# acrylic-sign_schematic.net
KiCad netlist of a schematic drawn in EAGLE
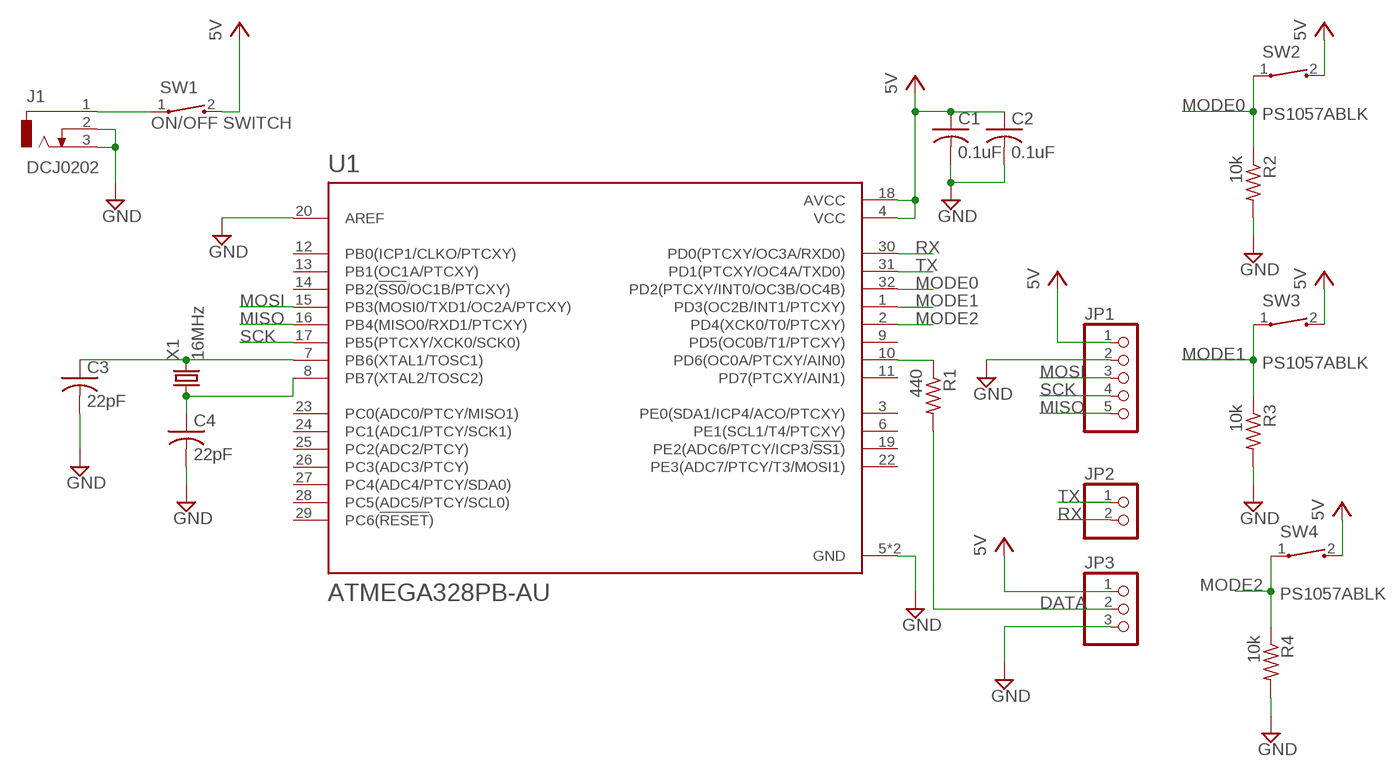
[diagram p0: schematic, sheet 1]

(export (version "E")
  (design (tool "Eeschema 10.0.6"))
  (components
    (comp (ref "C1")
      (value "0.1uF")
      (footprint "eagle-import:C0603")
      (libsource (lib "eagle-import") (part "C-USC0603"))
    )
    (comp (ref "C2")
      (value "0.1uF")
      (footprint "eagle-import:C0603")
      (libsource (lib "eagle-import") (part "C-USC0603"))
    )
    (comp (ref "C3")
      (value "22pF")
      (footprint "eagle-import:C0603")
      (libsource (lib "eagle-import") (part "C-USC0603"))
    )
    (comp (ref "C4")
      (value "22pF")
      (footprint "eagle-import:C0603")
      (libsource (lib "eagle-import") (part "C-USC0603"))
    )
    (comp (ref "J1")
      (value "DCJ0202")
      (footprint "eagle-import:DCJ0202")
      (libsource (lib "eagle-import") (part "DCJ0202"))
    )
    (comp (ref "JP1")
      (value "PINHD-1X5")
      (footprint "eagle-import:1X05")
      (libsource (lib "eagle-import") (part "PINHD-1X5"))
    )
    (comp (ref "JP2")
      (value "PINHD-1X2")
      (footprint "eagle-import:1X02")
      (libsource (lib "eagle-import") (part "PINHD-1X2"))
    )
    (comp (ref "JP3")
      (value "PINHD-1X3")
      (footprint "eagle-import:1X03")
      (libsource (lib "eagle-import") (part "PINHD-1X3"))
    )
    (comp (ref "R1")
      (value "440")
      (footprint "eagle-import:R0603")
      (libsource (lib "eagle-import") (part "R-US_R0603"))
    )
    (comp (ref "R2")
      (value "10k")
      (footprint "eagle-import:R0603")
      (libsource (lib "eagle-import") (part "R-US_R0603"))
    )
    (comp (ref "R3")
      (value "10k")
      (footprint "eagle-import:R0603")
      (libsource (lib "eagle-import") (part "R-US_R0603"))
    )
    (comp (ref "R4")
      (value "10k")
      (footprint "eagle-import:R0603")
      (libsource (lib "eagle-import") (part "R-US_R0603"))
    )
    (comp (ref "SW1")
      (value "AMAZON_SWITCH")
      (footprint "eagle-import:1X2-3.5MM")
      (libsource (lib "eagle-import") (part "AMAZON_SWITCH"))
    )
    (comp (ref "SW2")
      (value "PS1057ABLK")
      (footprint "eagle-import:1X2-3.5MM")
      (libsource (lib "eagle-import") (part "PS1057ABLK"))
    )
    (comp (ref "SW3")
      (value "PS1057ABLK")
      (footprint "eagle-import:1X2-3.5MM")
      (libsource (lib "eagle-import") (part "PS1057ABLK"))
    )
    (comp (ref "SW4")
      (value "PS1057ABLK")
      (footprint "eagle-import:1X2-3.5MM")
      (libsource (lib "eagle-import") (part "PS1057ABLK"))
    )
    (comp (ref "U1")
      (value "ATMEGA328PB-AU")
      (footprint "eagle-import:QFP80P900X900X120-32N")
      (fields (field (name "DIGI-KEY_PART_NUMBER") "ATMEGA328PB-AU-ND") (field (name "MF") "Microchip"))
      (libsource (lib "eagle-import") (part "ATMEGA328PB-AU"))
    )
    (comp (ref "X1")
      (value "16MHz")
      (footprint "eagle-import:2-SMD-5X3")
      (libsource (lib "eagle-import") (part "NX5032GA-16MHZ-STD-CSK-4"))
    )
  )
  (nets
    (net (code "1") (name "/DATA") (class "Default")
      (node (ref "JP3") (pin "2") (pinfunction "2_2") (pintype "passive"))
      (node (ref "R1") (pin "2") (pinfunction "2_2") (pintype "passive"))
    )
    (net (code "2") (name "/MISO") (class "Default")
      (node (ref "JP1") (pin "5") (pinfunction "5_5") (pintype "passive"))
      (node (ref "U1") (pin "16") (pinfunction "PB4(MISO0/RXD1/PTCXY)_16") (pintype "bidirectional"))
    )
    (net (code "3") (name "/MODE0") (class "Default")
      (node (ref "R2") (pin "1") (pinfunction "1_1") (pintype "passive"))
      (node (ref "SW2") (pin "1") (pinfunction "1_1") (pintype "passive"))
      (node (ref "U1") (pin "32") (pinfunction "PD2(PTCXY/INT0/OC3B/OC4B)_32") (pintype "bidirectional"))
    )
    (net (code "4") (name "/MODE1") (class "Default")
      (node (ref "R3") (pin "1") (pinfunction "1_1") (pintype "passive"))
      (node (ref "SW3") (pin "1") (pinfunction "1_1") (pintype "passive"))
      (node (ref "U1") (pin "1") (pinfunction "PD3(OC2B/INT1/PTCXY)_1") (pintype "bidirectional"))
    )
    (net (code "5") (name "/MODE2") (class "Default")
      (node (ref "R4") (pin "1") (pinfunction "1_1") (pintype "passive"))
      (node (ref "SW4") (pin "1") (pinfunction "1_1") (pintype "passive"))
      (node (ref "U1") (pin "2") (pinfunction "PD4(XCK0/T0/PTCXY)_2") (pintype "bidirectional"))
    )
    (net (code "6") (name "/MOSI") (class "Default")
      (node (ref "JP1") (pin "3") (pinfunction "3_3") (pintype "passive"))
      (node (ref "U1") (pin "15") (pinfunction "PB3(MOSI0/TXD1/OC2A/PTCXY)_15") (pintype "bidirectional"))
    )
    (net (code "7") (name "/RX") (class "Default")
      (node (ref "JP2") (pin "2") (pinfunction "2_2") (pintype "passive"))
      (node (ref "U1") (pin "30") (pinfunction "PD0(PTCXY/OC3A/RXD0)_30") (pintype "bidirectional"))
    )
    (net (code "8") (name "/SCK") (class "Default")
      (node (ref "JP1") (pin "4") (pinfunction "4_4") (pintype "passive"))
      (node (ref "U1") (pin "17") (pinfunction "PB5(PTCXY/XCK0/SCK0)_17") (pintype "bidirectional"))
    )
    (net (code "9") (name "/TX") (class "Default")
      (node (ref "JP2") (pin "1") (pinfunction "1_1") (pintype "passive"))
      (node (ref "U1") (pin "31") (pinfunction "PD1(PTCXY/OC4A/TXD0)_31") (pintype "bidirectional"))
    )
    (net (code "10") (name "5V") (class "Default")
      (node (ref "C1") (pin "1") (pinfunction "1_1") (pintype "passive"))
      (node (ref "C2") (pin "1") (pinfunction "1_1") (pintype "passive"))
      (node (ref "JP1") (pin "1") (pinfunction "1_1") (pintype "passive"))
      (node (ref "JP3") (pin "1") (pinfunction "1_1") (pintype "passive"))
      (node (ref "SW1") (pin "2") (pinfunction "2_2") (pintype "passive"))
      (node (ref "SW2") (pin "2") (pinfunction "2_2") (pintype "passive"))
      (node (ref "SW3") (pin "2") (pinfunction "2_2") (pintype "passive"))
      (node (ref "SW4") (pin "2") (pinfunction "2_2") (pintype "passive"))
      (node (ref "U1") (pin "18") (pinfunction "AVCC_18") (pintype "power_in"))
      (node (ref "U1") (pin "4") (pinfunction "VCC_4") (pintype "power_in"))
    )
    (net (code "11") (name "GND") (class "Default")
      (node (ref "C1") (pin "2") (pinfunction "2_2") (pintype "passive"))
      (node (ref "C2") (pin "2") (pinfunction "2_2") (pintype "passive"))
      (node (ref "C3") (pin "2") (pinfunction "2_2") (pintype "passive"))
      (node (ref "C4") (pin "2") (pinfunction "2_2") (pintype "passive"))
      (node (ref "J1") (pin "2") (pinfunction "2_2") (pintype "passive"))
      (node (ref "J1") (pin "3") (pinfunction "3_3") (pintype "passive"))
      (node (ref "JP1") (pin "2") (pinfunction "2_2") (pintype "passive"))
      (node (ref "JP3") (pin "3") (pinfunction "3_3") (pintype "passive"))
      (node (ref "R2") (pin "2") (pinfunction "2_2") (pintype "passive"))
      (node (ref "R3") (pin "2") (pinfunction "2_2") (pintype "passive"))
      (node (ref "R4") (pin "2") (pinfunction "2_2") (pintype "passive"))
      (node (ref "U1") (pin "20") (pinfunction "AREF_20") (pintype "input"))
      (node (ref "U1") (pin "21") (pinfunction "GND_21") (pintype "power_in"))
      (node (ref "U1") (pin "5") (pinfunction "GND_5") (pintype "power_in"))
    )
    (net (code "12") (name "Net-(J1-Pad1)") (class "Default")
      (node (ref "J1") (pin "1") (pinfunction "1_1") (pintype "passive"))
      (node (ref "SW1") (pin "1") (pinfunction "1_1") (pintype "passive"))
    )
    (net (code "13") (name "Net-(U1-PB6(XTAL1{slash}TOSC1))") (class "Default")
      (node (ref "C3") (pin "1") (pinfunction "1_1") (pintype "passive"))
      (node (ref "U1") (pin "7") (pinfunction "PB6(XTAL1/TOSC1)_7") (pintype "bidirectional"))
      (node (ref "X1") (pin "2") (pinfunction "2_2") (pintype "passive"))
    )
    (net (code "14") (name "Net-(U1-PB7(XTAL2{slash}TOSC2))") (class "Default")
      (node (ref "C4") (pin "1") (pinfunction "1_1") (pintype "passive"))
      (node (ref "U1") (pin "8") (pinfunction "PB7(XTAL2/TOSC2)_8") (pintype "bidirectional"))
      (node (ref "X1") (pin "1") (pinfunction "1_1") (pintype "passive"))
    )
    (net (code "15") (name "Net-(U1-PD6(OC0A{slash}PTCXY{slash}AIN0))") (class "Default")
      (node (ref "R1") (pin "1") (pinfunction "1_1") (pintype "passive"))
      (node (ref "U1") (pin "10") (pinfunction "PD6(OC0A/PTCXY/AIN0)_10") (pintype "bidirectional"))
    )
    (net (code "16") (name "unconnected-(U1-PB0(ICP1{slash}CLKO{slash}PTCXY)-Pad12)") (class "Default")
      (node (ref "U1") (pin "12") (pinfunction "PB0(ICP1/CLKO/PTCXY)_12") (pintype "bidirectional"))
    )
    (net (code "17") (name "unconnected-(U1-PB1(OC1A{slash}PTCXY)-Pad13)") (class "Default")
      (node (ref "U1") (pin "13") (pinfunction "PB1(OC1A/PTCXY)_13") (pintype "bidirectional"))
    )
    (net (code "18") (name "unconnected-(U1-PB2(~{SS0}{slash}OC1B{slash}PTCXY)-Pad14)") (class "Default")
      (node (ref "U1") (pin "14") (pinfunction "PB2(~{SS0}/OC1B/PTCXY)_14") (pintype "bidirectional"))
    )
    (net (code "19") (name "unconnected-(U1-PC0(ADC0{slash}PTCY{slash}MISO1)-Pad23)") (class "Default")
      (node (ref "U1") (pin "23") (pinfunction "PC0(ADC0/PTCY/MISO1)_23") (pintype "bidirectional"))
    )
    (net (code "20") (name "unconnected-(U1-PC1(ADC1{slash}PTCY{slash}SCK1)-Pad24)") (class "Default")
      (node (ref "U1") (pin "24") (pinfunction "PC1(ADC1/PTCY/SCK1)_24") (pintype "bidirectional"))
    )
    (net (code "21") (name "unconnected-(U1-PC2(ADC2{slash}PTCY)-Pad25)") (class "Default")
      (node (ref "U1") (pin "25") (pinfunction "PC2(ADC2/PTCY)_25") (pintype "bidirectional"))
    )
    (net (code "22") (name "unconnected-(U1-PC3(ADC3{slash}PTCY)-Pad26)") (class "Default")
      (node (ref "U1") (pin "26") (pinfunction "PC3(ADC3/PTCY)_26") (pintype "bidirectional"))
    )
    (net (code "23") (name "unconnected-(U1-PC4(ADC4{slash}PTCY{slash}SDA0)-Pad27)") (class "Default")
      (node (ref "U1") (pin "27") (pinfunction "PC4(ADC4/PTCY/SDA0)_27") (pintype "bidirectional"))
    )
    (net (code "24") (name "unconnected-(U1-PC5(ADC5{slash}PTCY{slash}SCL0)-Pad28)") (class "Default")
      (node (ref "U1") (pin "28") (pinfunction "PC5(ADC5/PTCY/SCL0)_28") (pintype "bidirectional"))
    )
    (net (code "25") (name "unconnected-(U1-PC6(~{RESET})-Pad29)") (class "Default")
      (node (ref "U1") (pin "29") (pinfunction "PC6(~{RESET})_29") (pintype "bidirectional"))
    )
    (net (code "26") (name "unconnected-(U1-PD5(OC0B{slash}T1{slash}PTCXY)-Pad9)") (class "Default")
      (node (ref "U1") (pin "9") (pinfunction "PD5(OC0B/T1/PTCXY)_9") (pintype "bidirectional"))
    )
    (net (code "27") (name "unconnected-(U1-PD7(PTCXY{slash}AIN1)-Pad11)") (class "Default")
      (node (ref "U1") (pin "11") (pinfunction "PD7(PTCXY/AIN1)_11") (pintype "bidirectional"))
    )
    (net (code "28") (name "unconnected-(U1-PE0(SDA1{slash}ICP4{slash}ACO{slash}PTCXY)-Pad3)") (class "Default")
      (node (ref "U1") (pin "3") (pinfunction "PE0(SDA1/ICP4/ACO/PTCXY)_3") (pintype "bidirectional"))
    )
    (net (code "29") (name "unconnected-(U1-PE1(SCL1{slash}T4{slash}PTCXY)-Pad6)") (class "Default")
      (node (ref "U1") (pin "6") (pinfunction "PE1(SCL1/T4/PTCXY)_6") (pintype "bidirectional"))
    )
    (net (code "30") (name "unconnected-(U1-PE2(ADC6{slash}PTCY{slash}ICP3{slash}~{SS1})-Pad19)") (class "Default")
      (node (ref "U1") (pin "19") (pinfunction "PE2(ADC6/PTCY/ICP3/~{SS1})_19") (pintype "bidirectional"))
    )
    (net (code "31") (name "unconnected-(U1-PE3(ADC7{slash}PTCY{slash}T3{slash}MOSI1)-Pad22)") (class "Default")
      (node (ref "U1") (pin "22") (pinfunction "PE3(ADC7/PTCY/T3/MOSI1)_22") (pintype "bidirectional"))
    )
  )
)
